# 1.net
KiCad netlist of a schematic drawn in EAGLE
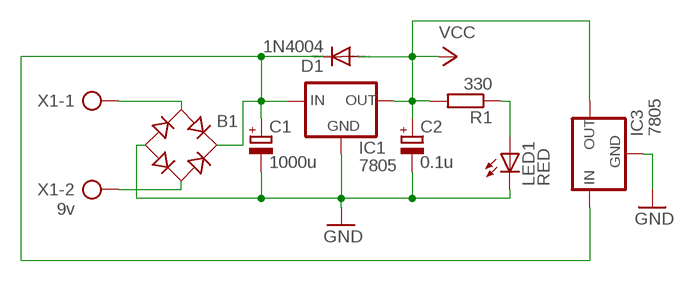
[diagram p0: schematic, sheet 1]
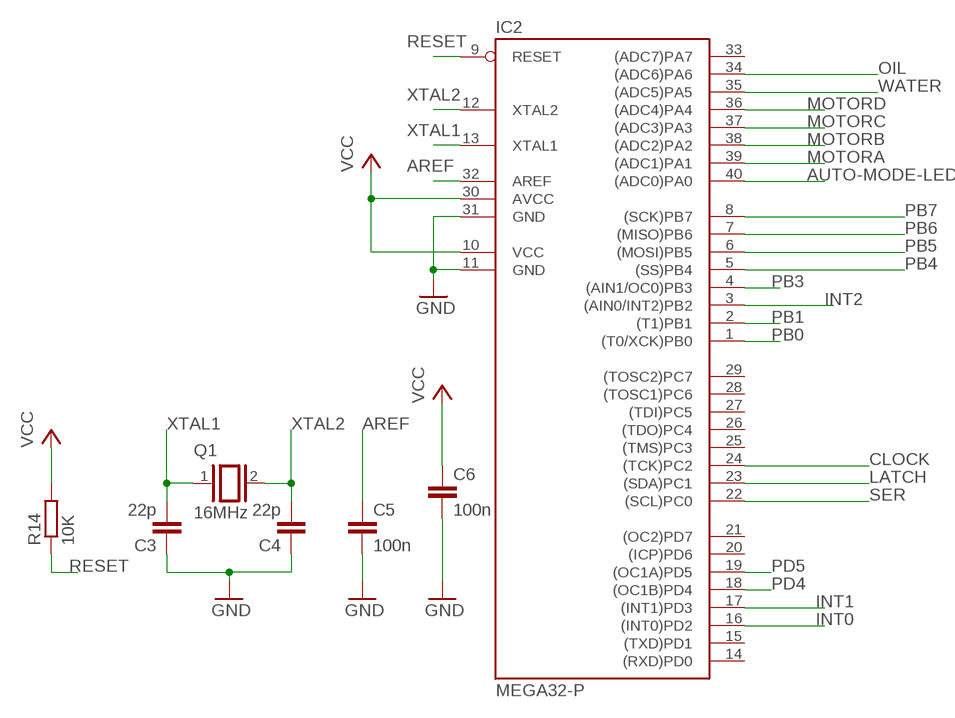
[diagram p1: schematic, sheet 2]
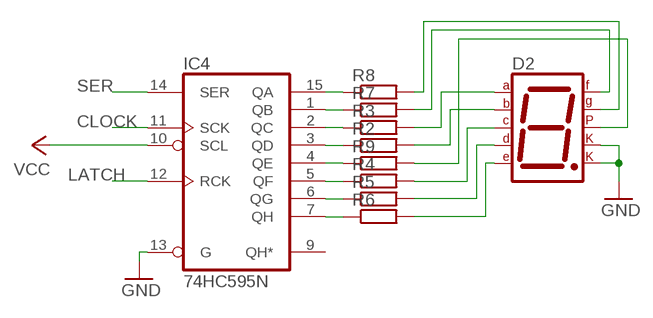
[diagram p2: schematic, sheet 3]
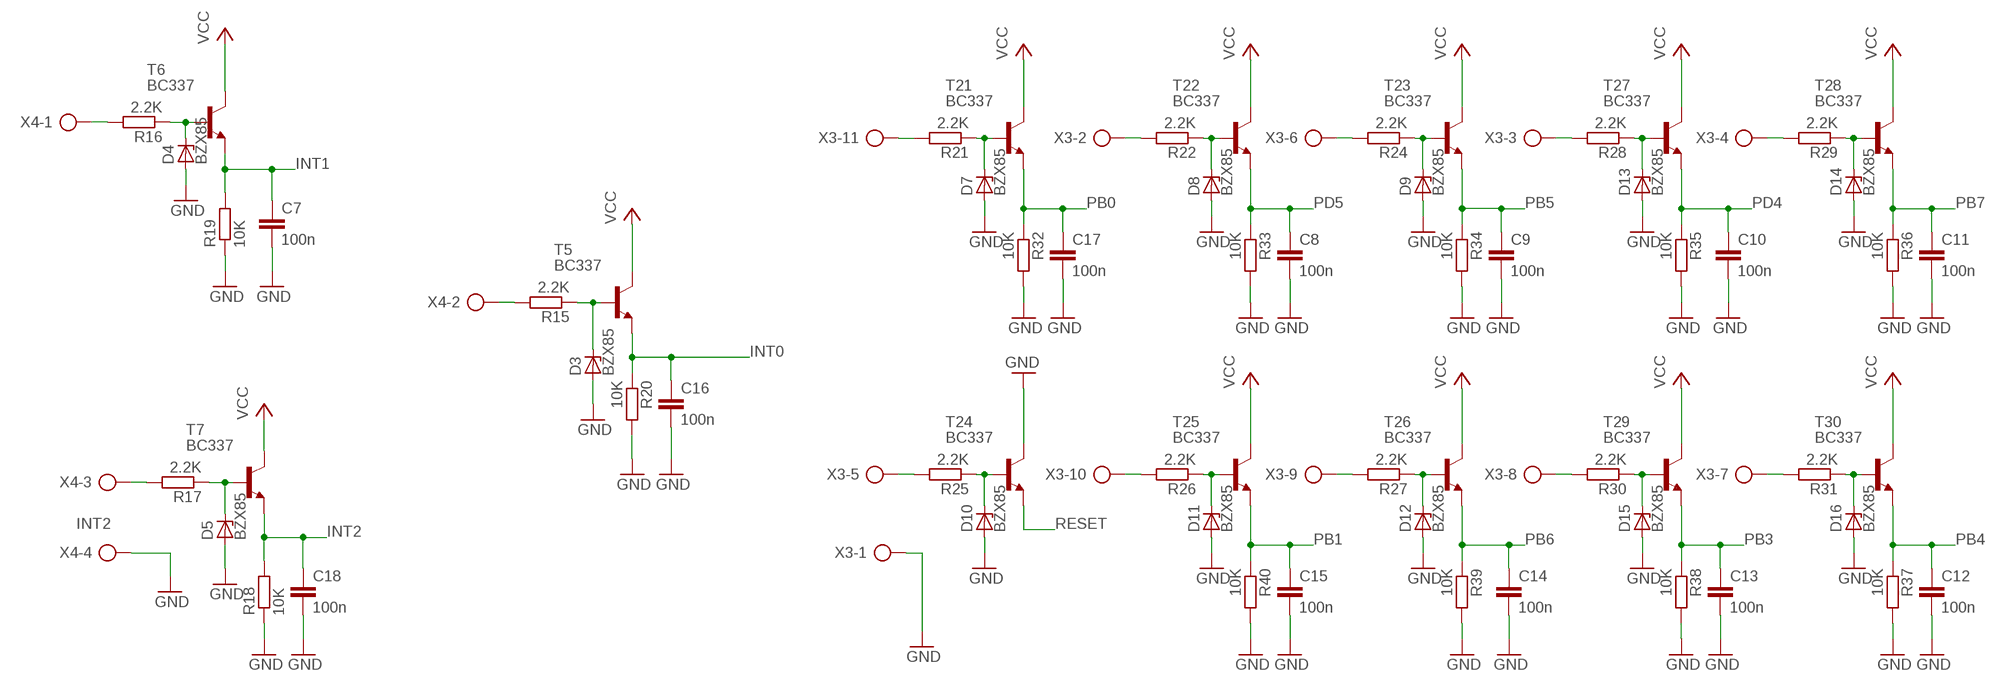
[diagram p3: schematic, sheet 4]
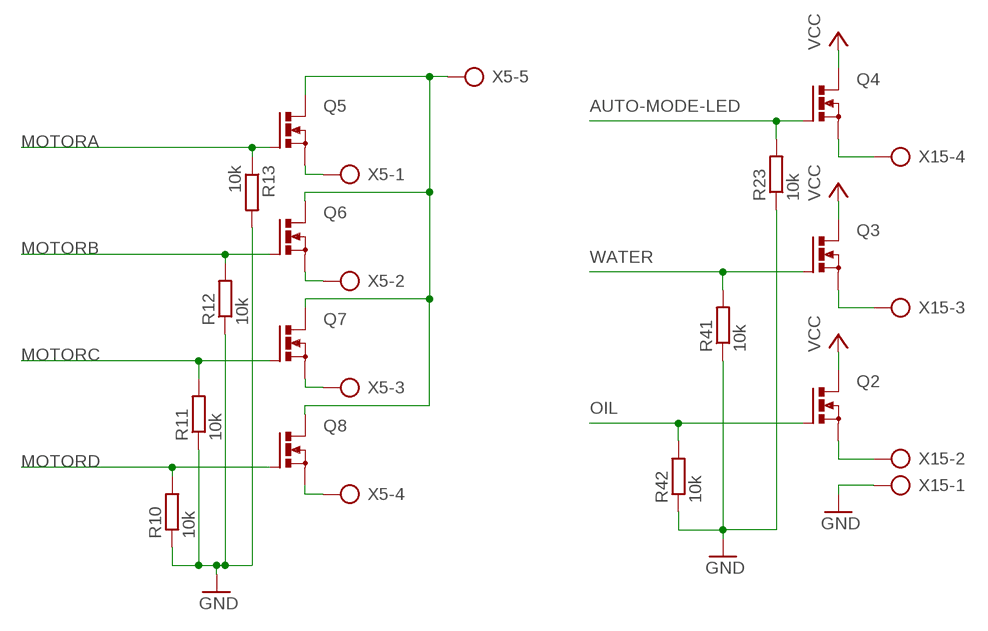
[diagram p4: schematic, sheet 5]

(export (version "E")
  (design (tool "Eeschema 10.0.6"))
  (components
    (comp (ref "Q2")
      (value "N-MOSFET-SO8S")
      (footprint "eagle-import:SO-08")
      (libsource (lib "eagle-import") (part "N-MOSFET-SO8S"))
    )
    (comp (ref "Q3")
      (value "N-MOSFET-SO8S")
      (footprint "eagle-import:SO-08")
      (libsource (lib "eagle-import") (part "N-MOSFET-SO8S"))
    )
    (comp (ref "Q4")
      (value "N-MOSFET-SO8S")
      (footprint "eagle-import:SO-08")
      (libsource (lib "eagle-import") (part "N-MOSFET-SO8S"))
    )
    (comp (ref "Q5")
      (value "N-MOSFET-SO8S")
      (footprint "eagle-import:SO-08")
      (libsource (lib "eagle-import") (part "N-MOSFET-SO8S"))
    )
    (comp (ref "Q6")
      (value "N-MOSFET-SO8S")
      (footprint "eagle-import:SO-08")
      (libsource (lib "eagle-import") (part "N-MOSFET-SO8S"))
    )
    (comp (ref "Q7")
      (value "N-MOSFET-SO8S")
      (footprint "eagle-import:SO-08")
      (libsource (lib "eagle-import") (part "N-MOSFET-SO8S"))
    )
    (comp (ref "Q8")
      (value "N-MOSFET-SO8S")
      (footprint "eagle-import:SO-08")
      (libsource (lib "eagle-import") (part "N-MOSFET-SO8S"))
    )
    (comp (ref "R10")
      (value "10k")
      (footprint "eagle-import:0204_7")
      (libsource (lib "eagle-import") (part "R-EU_0204/7"))
    )
    (comp (ref "R11")
      (value "10k")
      (footprint "eagle-import:0204_7")
      (libsource (lib "eagle-import") (part "R-EU_0204/7"))
    )
    (comp (ref "R12")
      (value "10k")
      (footprint "eagle-import:0204_7")
      (libsource (lib "eagle-import") (part "R-EU_0204/7"))
    )
    (comp (ref "R13")
      (value "10k")
      (footprint "eagle-import:0204_7")
      (libsource (lib "eagle-import") (part "R-EU_0204/7"))
    )
    (comp (ref "R23")
      (value "10k")
      (footprint "eagle-import:0204_7")
      (libsource (lib "eagle-import") (part "R-EU_0204/7"))
    )
    (comp (ref "R41")
      (value "10k")
      (footprint "eagle-import:0204_7")
      (libsource (lib "eagle-import") (part "R-EU_0204/7"))
    )
    (comp (ref "R42")
      (value "10k")
      (footprint "eagle-import:0204_7")
      (libsource (lib "eagle-import") (part "R-EU_0204/7"))
    )
    (comp (ref "X5")
      (value "AK500/5")
      (footprint "eagle-import:AK500_5")
      (libsource (lib "eagle-import") (part "AK500/5"))
    )
    (comp (ref "X15")
      (value "AK500/4")
      (footprint "eagle-import:AK500_4")
      (libsource (lib "eagle-import") (part "AK500/4"))
    )
    (comp (ref "C3")
      (value "22p")
      (footprint "eagle-import:C025-024X044")
      (libsource (lib "eagle-import") (part "C-EU025-024X044"))
    )
    (comp (ref "C4")
      (value "22p")
      (footprint "eagle-import:C025-024X044")
      (libsource (lib "eagle-import") (part "C-EU025-024X044"))
    )
    (comp (ref "C5")
      (value "100n")
      (footprint "eagle-import:C025-024X044")
      (libsource (lib "eagle-import") (part "C-EU025-024X044"))
    )
    (comp (ref "C6")
      (value "100n")
      (footprint "eagle-import:C025-024X044")
      (libsource (lib "eagle-import") (part "C-EU025-024X044"))
    )
    (comp (ref "IC2")
      (value "MEGA32-P")
      (footprint "eagle-import:DIL40")
      (fields (field (name "MPN") "ATMEGA32-16PU"))
      (libsource (lib "eagle-import") (part "MEGA32-P"))
    )
    (comp (ref "Q1")
      (value "16MHz")
      (footprint "eagle-import:Q")
      (libsource (lib "eagle-import") (part "XTAL"))
    )
    (comp (ref "R14")
      (value "10K")
      (footprint "eagle-import:0204_7")
      (libsource (lib "eagle-import") (part "R-EU_0204/7"))
    )
    (comp (ref "D2")
      (value "7SEG-CK")
      (footprint "eagle-import:7SEG-13")
      (libsource (lib "eagle-import") (part "7SEG-CK"))
    )
    (comp (ref "IC4")
      (value "74HC595N")
      (footprint "eagle-import:DIL16")
      (libsource (lib "eagle-import") (part "74595NHC"))
    )
    (comp (ref "R2")
      (value "R-EU_0204/7")
      (footprint "eagle-import:0204_7")
      (libsource (lib "eagle-import") (part "R-EU_0204/7"))
    )
    (comp (ref "R3")
      (value "R-EU_0204/7")
      (footprint "eagle-import:0204_7")
      (libsource (lib "eagle-import") (part "R-EU_0204/7"))
    )
    (comp (ref "R4")
      (value "R-EU_0204/7")
      (footprint "eagle-import:0204_7")
      (libsource (lib "eagle-import") (part "R-EU_0204/7"))
    )
    (comp (ref "R5")
      (value "R-EU_0204/7")
      (footprint "eagle-import:0204_7")
      (libsource (lib "eagle-import") (part "R-EU_0204/7"))
    )
    (comp (ref "R6")
      (value "R-EU_0204/7")
      (footprint "eagle-import:0204_7")
      (libsource (lib "eagle-import") (part "R-EU_0204/7"))
    )
    (comp (ref "R7")
      (value "R-EU_0204/7")
      (footprint "eagle-import:0204_7")
      (libsource (lib "eagle-import") (part "R-EU_0204/7"))
    )
    (comp (ref "R8")
      (value "R-EU_0204/7")
      (footprint "eagle-import:0204_7")
      (libsource (lib "eagle-import") (part "R-EU_0204/7"))
    )
    (comp (ref "R9")
      (value "R-EU_0204/7")
      (footprint "eagle-import:0204_7")
      (libsource (lib "eagle-import") (part "R-EU_0204/7"))
    )
    (comp (ref "B1")
      (value "RB1A")
      (footprint "eagle-import:RB1A")
      (libsource (lib "eagle-import") (part "RB1A"))
    )
    (comp (ref "C1")
      (value "1000u")
      (footprint "eagle-import:E3,5-8")
      (libsource (lib "eagle-import") (part "CPOL-EUE3.5-8"))
    )
    (comp (ref "C2")
      (value "0.1u")
      (footprint "eagle-import:E2-5")
      (libsource (lib "eagle-import") (part "CPOL-EUE2-5"))
    )
    (comp (ref "D1")
      (value "1N4004")
      (footprint "eagle-import:DO41-10")
      (libsource (lib "eagle-import") (part "1N4004"))
    )
    (comp (ref "IC1")
      (value "7805")
      (footprint "eagle-import:78XXS")
      (libsource (lib "eagle-import") (part "78XXS"))
    )
    (comp (ref "IC3")
      (value "7805")
      (footprint "eagle-import:78XXS")
      (libsource (lib "eagle-import") (part "78XXS"))
    )
    (comp (ref "LED1")
      (value "RED")
      (footprint "eagle-import:LED5MM")
      (libsource (lib "eagle-import") (part "LED5MM"))
    )
    (comp (ref "R1")
      (value "330")
      (footprint "eagle-import:0204_7")
      (libsource (lib "eagle-import") (part "R-EU_0204/7"))
    )
    (comp (ref "X1")
      (value "9v")
      (footprint "eagle-import:AK500_2")
      (libsource (lib "eagle-import") (part "AK500/2"))
    )
    (comp (ref "C7")
      (value "100n")
      (footprint "eagle-import:C025-024X044")
      (libsource (lib "eagle-import") (part "C-EU025-024X044"))
    )
    (comp (ref "C8")
      (value "100n")
      (footprint "eagle-import:C025-024X044")
      (libsource (lib "eagle-import") (part "C-EU025-024X044"))
    )
    (comp (ref "C9")
      (value "100n")
      (footprint "eagle-import:C025-024X044")
      (libsource (lib "eagle-import") (part "C-EU025-024X044"))
    )
    (comp (ref "C10")
      (value "100n")
      (footprint "eagle-import:C025-024X044")
      (libsource (lib "eagle-import") (part "C-EU025-024X044"))
    )
    (comp (ref "C11")
      (value "100n")
      (footprint "eagle-import:C025-024X044")
      (libsource (lib "eagle-import") (part "C-EU025-024X044"))
    )
    (comp (ref "C12")
      (value "100n")
      (footprint "eagle-import:C025-024X044")
      (libsource (lib "eagle-import") (part "C-EU025-024X044"))
    )
    (comp (ref "C13")
      (value "100n")
      (footprint "eagle-import:C025-024X044")
      (libsource (lib "eagle-import") (part "C-EU025-024X044"))
    )
    (comp (ref "C14")
      (value "100n")
      (footprint "eagle-import:C025-024X044")
      (libsource (lib "eagle-import") (part "C-EU025-024X044"))
    )
    (comp (ref "C15")
      (value "100n")
      (footprint "eagle-import:C025-024X044")
      (libsource (lib "eagle-import") (part "C-EU025-024X044"))
    )
    (comp (ref "C16")
      (value "100n")
      (footprint "eagle-import:C025-024X044")
      (libsource (lib "eagle-import") (part "C-EU025-024X044"))
    )
    (comp (ref "C17")
      (value "100n")
      (footprint "eagle-import:C025-024X044")
      (libsource (lib "eagle-import") (part "C-EU025-024X044"))
    )
    (comp (ref "C18")
      (value "100n")
      (footprint "eagle-import:C025-024X044")
      (libsource (lib "eagle-import") (part "C-EU025-024X044"))
    )
    (comp (ref "D3")
      (value "BZX85")
      (footprint "eagle-import:DO41Z10")
      (libsource (lib "eagle-import") (part "BZX85"))
    )
    (comp (ref "D4")
      (value "BZX85")
      (footprint "eagle-import:DO41Z10")
      (libsource (lib "eagle-import") (part "BZX85"))
    )
    (comp (ref "D5")
      (value "BZX85")
      (footprint "eagle-import:DO41Z10")
      (libsource (lib "eagle-import") (part "BZX85"))
    )
    (comp (ref "D7")
      (value "BZX85")
      (footprint "eagle-import:DO41Z10")
      (libsource (lib "eagle-import") (part "BZX85"))
    )
    (comp (ref "D8")
      (value "BZX85")
      (footprint "eagle-import:DO41Z10")
      (libsource (lib "eagle-import") (part "BZX85"))
    )
    (comp (ref "D9")
      (value "BZX85")
      (footprint "eagle-import:DO41Z10")
      (libsource (lib "eagle-import") (part "BZX85"))
    )
    (comp (ref "D10")
      (value "BZX85")
      (footprint "eagle-import:DO41Z10")
      (libsource (lib "eagle-import") (part "BZX85"))
    )
    (comp (ref "D11")
      (value "BZX85")
      (footprint "eagle-import:DO41Z10")
      (libsource (lib "eagle-import") (part "BZX85"))
    )
    (comp (ref "D12")
      (value "BZX85")
      (footprint "eagle-import:DO41Z10")
      (libsource (lib "eagle-import") (part "BZX85"))
    )
    (comp (ref "D13")
      (value "BZX85")
      (footprint "eagle-import:DO41Z10")
      (libsource (lib "eagle-import") (part "BZX85"))
    )
    (comp (ref "D14")
      (value "BZX85")
      (footprint "eagle-import:DO41Z10")
      (libsource (lib "eagle-import") (part "BZX85"))
    )
    (comp (ref "D15")
      (value "BZX85")
      (footprint "eagle-import:DO41Z10")
      (libsource (lib "eagle-import") (part "BZX85"))
    )
    (comp (ref "D16")
      (value "BZX85")
      (footprint "eagle-import:DO41Z10")
      (libsource (lib "eagle-import") (part "BZX85"))
    )
    (comp (ref "R15")
      (value "2.2K")
      (footprint "eagle-import:0207_10")
      (libsource (lib "eagle-import") (part "R-EU_0207/10"))
    )
    (comp (ref "R16")
      (value "2.2K")
      (footprint "eagle-import:0207_10")
      (libsource (lib "eagle-import") (part "R-EU_0207/10"))
    )
    (comp (ref "R17")
      (value "2.2K")
      (footprint "eagle-import:0207_10")
      (libsource (lib "eagle-import") (part "R-EU_0207/10"))
    )
    (comp (ref "R18")
      (value "10K")
      (footprint "eagle-import:0204_7")
      (libsource (lib "eagle-import") (part "R-EU_0204/7"))
    )
    (comp (ref "R19")
      (value "10K")
      (footprint "eagle-import:0204_7")
      (libsource (lib "eagle-import") (part "R-EU_0204/7"))
    )
    (comp (ref "R20")
      (value "10K")
      (footprint "eagle-import:0204_7")
      (libsource (lib "eagle-import") (part "R-EU_0204/7"))
    )
    (comp (ref "R21")
      (value "2.2K")
      (footprint "eagle-import:0207_10")
      (libsource (lib "eagle-import") (part "R-EU_0207/10"))
    )
    (comp (ref "R22")
      (value "2.2K")
      (footprint "eagle-import:0207_10")
      (libsource (lib "eagle-import") (part "R-EU_0207/10"))
    )
    (comp (ref "R24")
      (value "2.2K")
      (footprint "eagle-import:0207_10")
      (libsource (lib "eagle-import") (part "R-EU_0207/10"))
    )
    (comp (ref "R25")
      (value "2.2K")
      (footprint "eagle-import:0207_10")
      (libsource (lib "eagle-import") (part "R-EU_0207/10"))
    )
    (comp (ref "R26")
      (value "2.2K")
      (footprint "eagle-import:0207_10")
      (libsource (lib "eagle-import") (part "R-EU_0207/10"))
    )
    (comp (ref "R27")
      (value "2.2K")
      (footprint "eagle-import:0207_10")
      (libsource (lib "eagle-import") (part "R-EU_0207/10"))
    )
    (comp (ref "R28")
      (value "2.2K")
      (footprint "eagle-import:0207_10")
      (libsource (lib "eagle-import") (part "R-EU_0207/10"))
    )
    (comp (ref "R29")
      (value "2.2K")
      (footprint "eagle-import:0207_10")
      (libsource (lib "eagle-import") (part "R-EU_0207/10"))
    )
    (comp (ref "R30")
      (value "2.2K")
      (footprint "eagle-import:0207_10")
      (libsource (lib "eagle-import") (part "R-EU_0207/10"))
    )
    (comp (ref "R31")
      (value "2.2K")
      (footprint "eagle-import:0207_10")
      (libsource (lib "eagle-import") (part "R-EU_0207/10"))
    )
    (comp (ref "R32")
      (value "10K")
      (footprint "eagle-import:0204_7")
      (libsource (lib "eagle-import") (part "R-EU_0204/7"))
    )
    (comp (ref "R33")
      (value "10K")
      (footprint "eagle-import:0204_7")
      (libsource (lib "eagle-import") (part "R-EU_0204/7"))
    )
    (comp (ref "R34")
      (value "10K")
      (footprint "eagle-import:0204_7")
      (libsource (lib "eagle-import") (part "R-EU_0204/7"))
    )
    (comp (ref "R35")
      (value "10K")
      (footprint "eagle-import:0204_7")
      (libsource (lib "eagle-import") (part "R-EU_0204/7"))
    )
    (comp (ref "R36")
      (value "10K")
      (footprint "eagle-import:0204_7")
      (libsource (lib "eagle-import") (part "R-EU_0204/7"))
    )
    (comp (ref "R37")
      (value "10K")
      (footprint "eagle-import:0204_7")
      (libsource (lib "eagle-import") (part "R-EU_0204/7"))
    )
    (comp (ref "R38")
      (value "10K")
      (footprint "eagle-import:0204_7")
      (libsource (lib "eagle-import") (part "R-EU_0204/7"))
    )
    (comp (ref "R39")
      (value "10K")
      (footprint "eagle-import:0204_7")
      (libsource (lib "eagle-import") (part "R-EU_0204/7"))
    )
    (comp (ref "R40")
      (value "10K")
      (footprint "eagle-import:0204_7")
      (libsource (lib "eagle-import") (part "R-EU_0204/7"))
    )
    (comp (ref "T5")
      (value "BC337")
      (footprint "eagle-import:TO92")
      (libsource (lib "eagle-import") (part "BC337"))
    )
    (comp (ref "T6")
      (value "BC337")
      (footprint "eagle-import:TO92")
      (libsource (lib "eagle-import") (part "BC337"))
    )
    (comp (ref "T7")
      (value "BC337")
      (footprint "eagle-import:TO92")
      (libsource (lib "eagle-import") (part "BC337"))
    )
    (comp (ref "T21")
      (value "BC337")
      (footprint "eagle-import:TO92")
      (libsource (lib "eagle-import") (part "BC337"))
    )
    (comp (ref "T22")
      (value "BC337")
      (footprint "eagle-import:TO92")
      (libsource (lib "eagle-import") (part "BC337"))
    )
    (comp (ref "T23")
      (value "BC337")
      (footprint "eagle-import:TO92")
      (libsource (lib "eagle-import") (part "BC337"))
    )
    (comp (ref "T24")
      (value "BC337")
      (footprint "eagle-import:TO92")
      (libsource (lib "eagle-import") (part "BC337"))
    )
    (comp (ref "T25")
      (value "BC337")
      (footprint "eagle-import:TO92")
      (libsource (lib "eagle-import") (part "BC337"))
    )
    (comp (ref "T26")
      (value "BC337")
      (footprint "eagle-import:TO92")
      (libsource (lib "eagle-import") (part "BC337"))
    )
    (comp (ref "T27")
      (value "BC337")
      (footprint "eagle-import:TO92")
      (libsource (lib "eagle-import") (part "BC337"))
    )
    (comp (ref "T28")
      (value "BC337")
      (footprint "eagle-import:TO92")
      (libsource (lib "eagle-import") (part "BC337"))
    )
    (comp (ref "T29")
      (value "BC337")
      (footprint "eagle-import:TO92")
      (libsource (lib "eagle-import") (part "BC337"))
    )
    (comp (ref "T30")
      (value "BC337")
      (footprint "eagle-import:TO92")
      (libsource (lib "eagle-import") (part "BC337"))
    )
    (comp (ref "X3")
      (value "AK500/11")
      (footprint "eagle-import:AK500_11")
      (libsource (lib "eagle-import") (part "AK500/11"))
    )
    (comp (ref "X4")
      (value "AK500/4")
      (footprint "eagle-import:AK500_4")
      (libsource (lib "eagle-import") (part "AK500/4"))
    )
  )
  (nets
    (net (code "1") (name "AREF") (class "Default")
      (node (ref "C5") (pin "1") (pinfunction "1_1") (pintype "passive"))
      (node (ref "IC2") (pin "32") (pinfunction "AREF_32") (pintype "passive"))
    )
    (net (code "2") (name "AUTO-MODE-LED") (class "Default")
      (node (ref "IC2") (pin "40") (pinfunction "(ADC0)PA0_40") (pintype "bidirectional"))
      (node (ref "Q4") (pin "4") (pinfunction "G_4") (pintype "passive"))
      (node (ref "R23") (pin "2") (pinfunction "2_2") (pintype "passive"))
    )
    (net (code "3") (name "CLOCK") (class "Default")
      (node (ref "IC2") (pin "24") (pinfunction "(TCK)PC2_24") (pintype "bidirectional"))
      (node (ref "IC4") (pin "11") (pinfunction "SCK_11") (pintype "input"))
    )
    (net (code "4") (name "GND") (class "Default")
      (node (ref "B1") (pin "-") (pinfunction "-_-") (pintype "passive"))
      (node (ref "C1") (pin "-") (pinfunction "-_-") (pintype "passive"))
      (node (ref "C10") (pin "2") (pinfunction "2_2") (pintype "passive"))
      (node (ref "C11") (pin "2") (pinfunction "2_2") (pintype "passive"))
      (node (ref "C12") (pin "2") (pinfunction "2_2") (pintype "passive"))
      (node (ref "C13") (pin "2") (pinfunction "2_2") (pintype "passive"))
      (node (ref "C14") (pin "2") (pinfunction "2_2") (pintype "passive"))
      (node (ref "C15") (pin "2") (pinfunction "2_2") (pintype "passive"))
      (node (ref "C16") (pin "2") (pinfunction "2_2") (pintype "passive"))
      (node (ref "C17") (pin "2") (pinfunction "2_2") (pintype "passive"))
      (node (ref "C18") (pin "2") (pinfunction "2_2") (pintype "passive"))
      (node (ref "C2") (pin "-") (pinfunction "-_-") (pintype "passive"))
      (node (ref "C3") (pin "1") (pinfunction "1_1") (pintype "passive"))
      (node (ref "C4") (pin "1") (pinfunction "1_1") (pintype "passive"))
      (node (ref "C5") (pin "2") (pinfunction "2_2") (pintype "passive"))
      (node (ref "C6") (pin "2") (pinfunction "2_2") (pintype "passive"))
      (node (ref "C7") (pin "2") (pinfunction "2_2") (pintype "passive"))
      (node (ref "C8") (pin "2") (pinfunction "2_2") (pintype "passive"))
      (node (ref "C9") (pin "2") (pinfunction "2_2") (pintype "passive"))
      (node (ref "D10") (pin "A") (pinfunction "A_A") (pintype "passive"))
      (node (ref "D11") (pin "A") (pinfunction "A_A") (pintype "passive"))
      (node (ref "D12") (pin "A") (pinfunction "A_A") (pintype "passive"))
      (node (ref "D13") (pin "A") (pinfunction "A_A") (pintype "passive"))
      (node (ref "D14") (pin "A") (pinfunction "A_A") (pintype "passive"))
      (node (ref "D15") (pin "A") (pinfunction "A_A") (pintype "passive"))
      (node (ref "D16") (pin "A") (pinfunction "A_A") (pintype "passive"))
      (node (ref "D2") (pin "3") (pinfunction "CK1_3") (pintype "passive"))
      (node (ref "D2") (pin "8") (pinfunction "CK2_8") (pintype "passive"))
      (node (ref "D3") (pin "A") (pinfunction "A_A") (pintype "passive"))
      (node (ref "D4") (pin "A") (pinfunction "A_A") (pintype "passive"))
      (node (ref "D5") (pin "A") (pinfunction "A_A") (pintype "passive"))
      (node (ref "D7") (pin "A") (pinfunction "A_A") (pintype "passive"))
      (node (ref "D8") (pin "A") (pinfunction "A_A") (pintype "passive"))
      (node (ref "D9") (pin "A") (pinfunction "A_A") (pintype "passive"))
      (node (ref "IC1") (pin "GND") (pinfunction "GND_GND") (pintype "input"))
      (node (ref "IC2") (pin "11") (pinfunction "GND_11") (pintype "power_in"))
      (node (ref "IC2") (pin "31") (pinfunction "GND_31") (pintype "power_in"))
      (node (ref "IC3") (pin "GND") (pinfunction "GND_GND") (pintype "input"))
      (node (ref "IC4") (pin "13") (pinfunction "G_13") (pintype "input"))
      (node (ref "LED1") (pin "K") (pinfunction "C_K") (pintype "passive"))
      (node (ref "R10") (pin "1") (pinfunction "1_1") (pintype "passive"))
      (node (ref "R11") (pin "1") (pinfunction "1_1") (pintype "passive"))
      (node (ref "R12") (pin "1") (pinfunction "1_1") (pintype "passive"))
      (node (ref "R13") (pin "2") (pinfunction "2_2") (pintype "passive"))
      (node (ref "R18") (pin "1") (pinfunction "1_1") (pintype "passive"))
      (node (ref "R19") (pin "1") (pinfunction "1_1") (pintype "passive"))
      (node (ref "R20") (pin "2") (pinfunction "2_2") (pintype "passive"))
      (node (ref "R23") (pin "1") (pinfunction "1_1") (pintype "passive"))
      (node (ref "R32") (pin "2") (pinfunction "2_2") (pintype "passive"))
      (node (ref "R33") (pin "2") (pinfunction "2_2") (pintype "passive"))
      (node (ref "R34") (pin "2") (pinfunction "2_2") (pintype "passive"))
      (node (ref "R35") (pin "2") (pinfunction "2_2") (pintype "passive"))
      (node (ref "R36") (pin "2") (pinfunction "2_2") (pintype "passive"))
      (node (ref "R37") (pin "2") (pinfunction "2_2") (pintype "passive"))
      (node (ref "R38") (pin "2") (pinfunction "2_2") (pintype "passive"))
      (node (ref "R39") (pin "2") (pinfunction "2_2") (pintype "passive"))
      (node (ref "R40") (pin "2") (pinfunction "2_2") (pintype "passive"))
      (node (ref "R41") (pin "1") (pinfunction "1_1") (pintype "passive"))
      (node (ref "R42") (pin "1") (pinfunction "1_1") (pintype "passive"))
      (node (ref "T24") (pin "3") (pinfunction "C_3") (pintype "passive"))
      (node (ref "X15") (pin "1") (pinfunction "KL_1") (pintype "passive"))
      (node (ref "X3") (pin "1") (pinfunction "KL_1") (pintype "passive"))
      (node (ref "X4") (pin "4") (pinfunction "KL_4") (pintype "passive"))
    )
    (net (code "5") (name "INT0") (class "Default")
      (node (ref "C16") (pin "1") (pinfunction "1_1") (pintype "passive"))
      (node (ref "IC2") (pin "16") (pinfunction "(INT0)PD2_16") (pintype "bidirectional"))
      (node (ref "R20") (pin "1") (pinfunction "1_1") (pintype "passive"))
      (node (ref "T5") (pin "1") (pinfunction "E_1") (pintype "passive"))
    )
    (net (code "6") (name "INT1") (class "Default")
      (node (ref "C7") (pin "1") (pinfunction "1_1") (pintype "passive"))
      (node (ref "IC2") (pin "17") (pinfunction "(INT1)PD3_17") (pintype "bidirectional"))
      (node (ref "R19") (pin "2") (pinfunction "2_2") (pintype "passive"))
      (node (ref "T6") (pin "1") (pinfunction "E_1") (pintype "passive"))
    )
    (net (code "7") (name "INT2") (class "Default")
      (node (ref "C18") (pin "1") (pinfunction "1_1") (pintype "passive"))
      (node (ref "IC2") (pin "3") (pinfunction "(AIN0/INT2)PB2_3") (pintype "bidirectional"))
      (node (ref "R18") (pin "2") (pinfunction "2_2") (pintype "passive"))
      (node (ref "T7") (pin "1") (pinfunction "E_1") (pintype "passive"))
    )
    (net (code "8") (name "LATCH") (class "Default")
      (node (ref "IC2") (pin "23") (pinfunction "(SDA)PC1_23") (pintype "bidirectional"))
      (node (ref "IC4") (pin "12") (pinfunction "RCK_12") (pintype "input"))
    )
    (net (code "9") (name "MOTORA") (class "Default")
      (node (ref "IC2") (pin "39") (pinfunction "(ADC1)PA1_39") (pintype "bidirectional"))
      (node (ref "Q5") (pin "4") (pinfunction "G_4") (pintype "passive"))
      (node (ref "R13") (pin "1") (pinfunction "1_1") (pintype "passive"))
    )
    (net (code "10") (name "MOTORB") (class "Default")
      (node (ref "IC2") (pin "38") (pinfunction "(ADC2)PA2_38") (pintype "bidirectional"))
      (node (ref "Q6") (pin "4") (pinfunction "G_4") (pintype "passive"))
      (node (ref "R12") (pin "2") (pinfunction "2_2") (pintype "passive"))
    )
    (net (code "11") (name "MOTORC") (class "Default")
      (node (ref "IC2") (pin "37") (pinfunction "(ADC3)PA3_37") (pintype "bidirectional"))
      (node (ref "Q7") (pin "4") (pinfunction "G_4") (pintype "passive"))
      (node (ref "R11") (pin "2") (pinfunction "2_2") (pintype "passive"))
    )
    (net (code "12") (name "MOTORD") (class "Default")
      (node (ref "IC2") (pin "36") (pinfunction "(ADC4)PA4_36") (pintype "bidirectional"))
      (node (ref "Q8") (pin "4") (pinfunction "G_4") (pintype "passive"))
      (node (ref "R10") (pin "2") (pinfunction "2_2") (pintype "passive"))
    )
    (net (code "13") (name "Net-(B1-Pad+)") (class "Default")
      (node (ref "B1") (pin "+") (pinfunction "+_+") (pintype "passive"))
      (node (ref "C1") (pin "+") (pinfunction "+_+") (pintype "passive"))
      (node (ref "D1") (pin "C") (pinfunction "C_C") (pintype "passive"))
      (node (ref "IC1") (pin "IN") (pinfunction "IN_IN") (pintype "input"))
      (node (ref "IC3") (pin "IN") (pinfunction "IN_IN") (pintype "input"))
    )
    (net (code "14") (name "Net-(D2-A)") (class "Default")
      (node (ref "D2") (pin "7") (pinfunction "A_7") (pintype "passive"))
      (node (ref "R3") (pin "2") (pinfunction "2_2") (pintype "passive"))
    )
    (net (code "15") (name "Net-(D2-B)") (class "Default")
      (node (ref "D2") (pin "6") (pinfunction "B_6") (pintype "passive"))
      (node (ref "R2") (pin "2") (pinfunction "2_2") (pintype "passive"))
    )
    (net (code "16") (name "Net-(D2-C)") (class "Default")
      (node (ref "D2") (pin "4") (pinfunction "C_4") (pintype "passive"))
      (node (ref "R4") (pin "2") (pinfunction "2_2") (pintype "passive"))
    )
    (net (code "17") (name "Net-(D2-D)") (class "Default")
      (node (ref "D2") (pin "2") (pinfunction "D_2") (pintype "passive"))
      (node (ref "R5") (pin "2") (pinfunction "2_2") (pintype "passive"))
    )
    (net (code "18") (name "Net-(D2-DP)") (class "Default")
      (node (ref "D2") (pin "5") (pinfunction "DP_5") (pintype "passive"))
      (node (ref "R9") (pin "2") (pinfunction "2_2") (pintype "passive"))
    )
    (net (code "19") (name "Net-(D2-E)") (class "Default")
      (node (ref "D2") (pin "1") (pinfunction "E_1") (pintype "passive"))
      (node (ref "R6") (pin "2") (pinfunction "2_2") (pintype "passive"))
    )
    (net (code "20") (name "Net-(D2-F)") (class "Default")
      (node (ref "D2") (pin "9") (pinfunction "F_9") (pintype "passive"))
      (node (ref "R7") (pin "2") (pinfunction "2_2") (pintype "passive"))
    )
    (net (code "21") (name "Net-(D2-G)") (class "Default")
      (node (ref "D2") (pin "10") (pinfunction "G_10") (pintype "passive"))
      (node (ref "R8") (pin "2") (pinfunction "2_2") (pintype "passive"))
    )
    (net (code "22") (name "Net-(IC4A-QA)") (class "Default")
      (node (ref "IC4") (pin "15") (pinfunction "QA_15") (pintype "tri_state"))
      (node (ref "R8") (pin "1") (pinfunction "1_1") (pintype "passive"))
    )
    (net (code "23") (name "Net-(IC4A-QB)") (class "Default")
      (node (ref "IC4") (pin "1") (pinfunction "QB_1") (pintype "tri_state"))
      (node (ref "R7") (pin "1") (pinfunction "1_1") (pintype "passive"))
    )
    (net (code "24") (name "Net-(IC4A-QC)") (class "Default")
      (node (ref "IC4") (pin "2") (pinfunction "QC_2") (pintype "tri_state"))
      (node (ref "R3") (pin "1") (pinfunction "1_1") (pintype "passive"))
    )
    (net (code "25") (name "Net-(IC4A-QD)") (class "Default")
      (node (ref "IC4") (pin "3") (pinfunction "QD_3") (pintype "tri_state"))
      (node (ref "R2") (pin "1") (pinfunction "1_1") (pintype "passive"))
    )
    (net (code "26") (name "Net-(IC4A-QE)") (class "Default")
      (node (ref "IC4") (pin "4") (pinfunction "QE_4") (pintype "tri_state"))
      (node (ref "R9") (pin "1") (pinfunction "1_1") (pintype "passive"))
    )
    (net (code "27") (name "Net-(IC4A-QF)") (class "Default")
      (node (ref "IC4") (pin "5") (pinfunction "QF_5") (pintype "tri_state"))
      (node (ref "R4") (pin "1") (pinfunction "1_1") (pintype "passive"))
    )
    (net (code "28") (name "Net-(IC4A-QG)") (class "Default")
      (node (ref "IC4") (pin "6") (pinfunction "QG_6") (pintype "tri_state"))
      (node (ref "R5") (pin "1") (pinfunction "1_1") (pintype "passive"))
    )
    (net (code "29") (name "Net-(IC4A-QH)") (class "Default")
      (node (ref "IC4") (pin "7") (pinfunction "QH_7") (pintype "tri_state"))
      (node (ref "R6") (pin "1") (pinfunction "1_1") (pintype "passive"))
    )
    (net (code "30") (name "Net-(LED1-PadA)") (class "Default")
      (node (ref "LED1") (pin "A") (pinfunction "A_A") (pintype "passive"))
      (node (ref "R1") (pin "1") (pinfunction "1_1") (pintype "passive"))
    )
    (net (code "31") (name "Net-(T5-B)") (class "Default")
      (node (ref "D3") (pin "C") (pinfunction "C_C") (pintype "passive"))
      (node (ref "R15") (pin "1") (pinfunction "1_1") (pintype "passive"))
      (node (ref "T5") (pin "2") (pinfunction "B_2") (pintype "passive"))
    )
    (net (code "32") (name "Net-(T6-B)") (class "Default")
      (node (ref "D4") (pin "C") (pinfunction "C_C") (pintype "passive"))
      (node (ref "R16") (pin "1") (pinfunction "1_1") (pintype "passive"))
      (node (ref "T6") (pin "2") (pinfunction "B_2") (pintype "passive"))
    )
    (net (code "33") (name "Net-(T7-B)") (class "Default")
      (node (ref "D5") (pin "C") (pinfunction "C_C") (pintype "passive"))
      (node (ref "R17") (pin "1") (pinfunction "1_1") (pintype "passive"))
      (node (ref "T7") (pin "2") (pinfunction "B_2") (pintype "passive"))
    )
    (net (code "34") (name "Net-(T21-B)") (class "Default")
      (node (ref "D7") (pin "C") (pinfunction "C_C") (pintype "passive"))
      (node (ref "R21") (pin "1") (pinfunction "1_1") (pintype "passive"))
      (node (ref "T21") (pin "2") (pinfunction "B_2") (pintype "passive"))
    )
    (net (code "35") (name "Net-(T22-B)") (class "Default")
      (node (ref "D8") (pin "C") (pinfunction "C_C") (pintype "passive"))
      (node (ref "R22") (pin "1") (pinfunction "1_1") (pintype "passive"))
      (node (ref "T22") (pin "2") (pinfunction "B_2") (pintype "passive"))
    )
    (net (code "36") (name "Net-(T23-B)") (class "Default")
      (node (ref "D9") (pin "C") (pinfunction "C_C") (pintype "passive"))
      (node (ref "R24") (pin "1") (pinfunction "1_1") (pintype "passive"))
      (node (ref "T23") (pin "2") (pinfunction "B_2") (pintype "passive"))
    )
    (net (code "37") (name "Net-(T24-B)") (class "Default")
      (node (ref "D10") (pin "C") (pinfunction "C_C") (pintype "passive"))
      (node (ref "R25") (pin "1") (pinfunction "1_1") (pintype "passive"))
      (node (ref "T24") (pin "2") (pinfunction "B_2") (pintype "passive"))
    )
    (net (code "38") (name "Net-(T25-B)") (class "Default")
      (node (ref "D11") (pin "C") (pinfunction "C_C") (pintype "passive"))
      (node (ref "R26") (pin "1") (pinfunction "1_1") (pintype "passive"))
      (node (ref "T25") (pin "2") (pinfunction "B_2") (pintype "passive"))
    )
    (net (code "39") (name "Net-(T26-B)") (class "Default")
      (node (ref "D12") (pin "C") (pinfunction "C_C") (pintype "passive"))
      (node (ref "R27") (pin "1") (pinfunction "1_1") (pintype "passive"))
      (node (ref "T26") (pin "2") (pinfunction "B_2") (pintype "passive"))
    )
    (net (code "40") (name "Net-(T27-B)") (class "Default")
      (node (ref "D13") (pin "C") (pinfunction "C_C") (pintype "passive"))
      (node (ref "R28") (pin "1") (pinfunction "1_1") (pintype "passive"))
      (node (ref "T27") (pin "2") (pinfunction "B_2") (pintype "passive"))
    )
    (net (code "41") (name "Net-(T28-B)") (class "Default")
      (node (ref "D14") (pin "C") (pinfunction "C_C") (pintype "passive"))
      (node (ref "R29") (pin "1") (pinfunction "1_1") (pintype "passive"))
      (node (ref "T28") (pin "2") (pinfunction "B_2") (pintype "passive"))
    )
    (net (code "42") (name "Net-(T29-B)") (class "Default")
      (node (ref "D15") (pin "C") (pinfunction "C_C") (pintype "passive"))
      (node (ref "R30") (pin "1") (pinfunction "1_1") (pintype "passive"))
      (node (ref "T29") (pin "2") (pinfunction "B_2") (pintype "passive"))
    )
    (net (code "43") (name "Net-(T30-B)") (class "Default")
      (node (ref "D16") (pin "C") (pinfunction "C_C") (pintype "passive"))
      (node (ref "R31") (pin "1") (pinfunction "1_1") (pintype "passive"))
      (node (ref "T30") (pin "2") (pinfunction "B_2") (pintype "passive"))
    )
    (net (code "44") (name "Net-(X1A-KL)") (class "Default")
      (node (ref "B1") (pin "AC1") (pinfunction "AC1_AC1") (pintype "passive"))
      (node (ref "X1") (pin "1") (pinfunction "KL_1") (pintype "passive"))
    )
    (net (code "45") (name "Net-(X1B-KL)") (class "Default")
      (node (ref "B1") (pin "AC2") (pinfunction "AC2_AC2") (pintype "passive"))
      (node (ref "X1") (pin "2") (pinfunction "KL_2") (pintype "passive"))
    )
    (net (code "46") (name "Net-(X3B-KL)") (class "Default")
      (node (ref "R26") (pin "2") (pinfunction "2_2") (pintype "passive"))
      (node (ref "X3") (pin "10") (pinfunction "KL_10") (pintype "passive"))
    )
    (net (code "47") (name "Net-(X3C-KL)") (class "Default")
      (node (ref "R21") (pin "2") (pinfunction "2_2") (pintype "passive"))
      (node (ref "X3") (pin "11") (pinfunction "KL_11") (pintype "passive"))
    )
    (net (code "48") (name "Net-(X3D-KL)") (class "Default")
      (node (ref "R22") (pin "2") (pinfunction "2_2") (pintype "passive"))
      (node (ref "X3") (pin "2") (pinfunction "KL_2") (pintype "passive"))
    )
    (net (code "49") (name "Net-(X3E-KL)") (class "Default")
      (node (ref "R28") (pin "2") (pinfunction "2_2") (pintype "passive"))
      (node (ref "X3") (pin "3") (pinfunction "KL_3") (pintype "passive"))
    )
    (net (code "50") (name "Net-(X3F-KL)") (class "Default")
      (node (ref "R29") (pin "2") (pinfunction "2_2") (pintype "passive"))
      (node (ref "X3") (pin "4") (pinfunction "KL_4") (pintype "passive"))
    )
    (net (code "51") (name "Net-(X3G-KL)") (class "Default")
      (node (ref "R25") (pin "2") (pinfunction "2_2") (pintype "passive"))
      (node (ref "X3") (pin "5") (pinfunction "KL_5") (pintype "passive"))
    )
    (net (code "52") (name "Net-(X3H-KL)") (class "Default")
      (node (ref "R24") (pin "2") (pinfunction "2_2") (pintype "passive"))
      (node (ref "X3") (pin "6") (pinfunction "KL_6") (pintype "passive"))
    )
    (net (code "53") (name "Net-(X3I-KL)") (class "Default")
      (node (ref "R31") (pin "2") (pinfunction "2_2") (pintype "passive"))
      (node (ref "X3") (pin "7") (pinfunction "KL_7") (pintype "passive"))
    )
    (net (code "54") (name "Net-(X3J-KL)") (class "Default")
      (node (ref "R30") (pin "2") (pinfunction "2_2") (pintype "passive"))
      (node (ref "X3") (pin "8") (pinfunction "KL_8") (pintype "passive"))
    )
    (net (code "55") (name "Net-(X3K-KL)") (class "Default")
      (node (ref "R27") (pin "2") (pinfunction "2_2") (pintype "passive"))
      (node (ref "X3") (pin "9") (pinfunction "KL_9") (pintype "passive"))
    )
    (net (code "56") (name "Net-(X4A-KL)") (class "Default")
      (node (ref "R16") (pin "2") (pinfunction "2_2") (pintype "passive"))
      (node (ref "X4") (pin "1") (pinfunction "KL_1") (pintype "passive"))
    )
    (net (code "57") (name "Net-(X4B-KL)") (class "Default")
      (node (ref "R15") (pin "2") (pinfunction "2_2") (pintype "passive"))
      (node (ref "X4") (pin "2") (pinfunction "KL_2") (pintype "passive"))
    )
    (net (code "58") (name "Net-(X4C-KL)") (class "Default")
      (node (ref "R17") (pin "2") (pinfunction "2_2") (pintype "passive"))
      (node (ref "X4") (pin "3") (pinfunction "KL_3") (pintype "passive"))
    )
    (net (code "59") (name "Net-(X5A-KL)") (class "Default")
      (node (ref "Q5") (pin "1") (pinfunction "S_1") (pintype "passive"))
      (node (ref "Q5") (pin "2") (pinfunction "S_2") (pintype "passive"))
      (node (ref "Q5") (pin "3") (pinfunction "S_3") (pintype "passive"))
      (node (ref "X5") (pin "1") (pinfunction "KL_1") (pintype "passive"))
    )
    (net (code "60") (name "Net-(X5B-KL)") (class "Default")
      (node (ref "Q6") (pin "1") (pinfunction "S_1") (pintype "passive"))
      (node (ref "Q6") (pin "2") (pinfunction "S_2") (pintype "passive"))
      (node (ref "Q6") (pin "3") (pinfunction "S_3") (pintype "passive"))
      (node (ref "X5") (pin "2") (pinfunction "KL_2") (pintype "passive"))
    )
    (net (code "61") (name "Net-(X5C-KL)") (class "Default")
      (node (ref "Q7") (pin "1") (pinfunction "S_1") (pintype "passive"))
      (node (ref "Q7") (pin "2") (pinfunction "S_2") (pintype "passive"))
      (node (ref "Q7") (pin "3") (pinfunction "S_3") (pintype "passive"))
      (node (ref "X5") (pin "3") (pinfunction "KL_3") (pintype "passive"))
    )
    (net (code "62") (name "Net-(X5D-KL)") (class "Default")
      (node (ref "Q8") (pin "1") (pinfunction "S_1") (pintype "passive"))
      (node (ref "Q8") (pin "2") (pinfunction "S_2") (pintype "passive"))
      (node (ref "Q8") (pin "3") (pinfunction "S_3") (pintype "passive"))
      (node (ref "X5") (pin "4") (pinfunction "KL_4") (pintype "passive"))
    )
    (net (code "63") (name "Net-(X5E-KL)") (class "Default")
      (node (ref "Q5") (pin "5") (pinfunction "D_5") (pintype "passive"))
      (node (ref "Q5") (pin "6") (pinfunction "D_6") (pintype "passive"))
      (node (ref "Q5") (pin "7") (pinfunction "D_7") (pintype "passive"))
      (node (ref "Q5") (pin "8") (pinfunction "D_8") (pintype "passive"))
      (node (ref "Q6") (pin "5") (pinfunction "D_5") (pintype "passive"))
      (node (ref "Q6") (pin "6") (pinfunction "D_6") (pintype "passive"))
      (node (ref "Q6") (pin "7") (pinfunction "D_7") (pintype "passive"))
      (node (ref "Q6") (pin "8") (pinfunction "D_8") (pintype "passive"))
      (node (ref "Q7") (pin "5") (pinfunction "D_5") (pintype "passive"))
      (node (ref "Q7") (pin "6") (pinfunction "D_6") (pintype "passive"))
      (node (ref "Q7") (pin "7") (pinfunction "D_7") (pintype "passive"))
      (node (ref "Q7") (pin "8") (pinfunction "D_8") (pintype "passive"))
      (node (ref "Q8") (pin "5") (pinfunction "D_5") (pintype "passive"))
      (node (ref "Q8") (pin "6") (pinfunction "D_6") (pintype "passive"))
      (node (ref "Q8") (pin "7") (pinfunction "D_7") (pintype "passive"))
      (node (ref "Q8") (pin "8") (pinfunction "D_8") (pintype "passive"))
      (node (ref "X5") (pin "5") (pinfunction "KL_5") (pintype "passive"))
    )
    (net (code "64") (name "Net-(X15B-KL)") (class "Default")
      (node (ref "Q2") (pin "1") (pinfunction "S_1") (pintype "passive"))
      (node (ref "Q2") (pin "2") (pinfunction "S_2") (pintype "passive"))
      (node (ref "Q2") (pin "3") (pinfunction "S_3") (pintype "passive"))
      (node (ref "X15") (pin "2") (pinfunction "KL_2") (pintype "passive"))
    )
    (net (code "65") (name "Net-(X15C-KL)") (class "Default")
      (node (ref "Q3") (pin "1") (pinfunction "S_1") (pintype "passive"))
      (node (ref "Q3") (pin "2") (pinfunction "S_2") (pintype "passive"))
      (node (ref "Q3") (pin "3") (pinfunction "S_3") (pintype "passive"))
      (node (ref "X15") (pin "3") (pinfunction "KL_3") (pintype "passive"))
    )
    (net (code "66") (name "Net-(X15D-KL)") (class "Default")
      (node (ref "Q4") (pin "1") (pinfunction "S_1") (pintype "passive"))
      (node (ref "Q4") (pin "2") (pinfunction "S_2") (pintype "passive"))
      (node (ref "Q4") (pin "3") (pinfunction "S_3") (pintype "passive"))
      (node (ref "X15") (pin "4") (pinfunction "KL_4") (pintype "passive"))
    )
    (net (code "67") (name "OIL") (class "Default")
      (node (ref "IC2") (pin "34") (pinfunction "(ADC6)PA6_34") (pintype "bidirectional"))
      (node (ref "Q2") (pin "4") (pinfunction "G_4") (pintype "passive"))
      (node (ref "R42") (pin "2") (pinfunction "2_2") (pintype "passive"))
    )
    (net (code "68") (name "PB0") (class "Default")
      (node (ref "C17") (pin "1") (pinfunction "1_1") (pintype "passive"))
      (node (ref "IC2") (pin "1") (pinfunction "(T0/XCK)PB0_1") (pintype "bidirectional"))
      (node (ref "R32") (pin "1") (pinfunction "1_1") (pintype "passive"))
      (node (ref "T21") (pin "1") (pinfunction "E_1") (pintype "passive"))
    )
    (net (code "69") (name "PB1") (class "Default")
      (node (ref "C15") (pin "1") (pinfunction "1_1") (pintype "passive"))
      (node (ref "IC2") (pin "2") (pinfunction "(T1)PB1_2") (pintype "bidirectional"))
      (node (ref "R40") (pin "1") (pinfunction "1_1") (pintype "passive"))
      (node (ref "T25") (pin "1") (pinfunction "E_1") (pintype "passive"))
    )
    (net (code "70") (name "PB3") (class "Default")
      (node (ref "C13") (pin "1") (pinfunction "1_1") (pintype "passive"))
      (node (ref "IC2") (pin "4") (pinfunction "(AIN1/OC0)PB3_4") (pintype "bidirectional"))
      (node (ref "R38") (pin "1") (pinfunction "1_1") (pintype "passive"))
      (node (ref "T29") (pin "1") (pinfunction "E_1") (pintype "passive"))
    )
    (net (code "71") (name "PB4") (class "Default")
      (node (ref "C12") (pin "1") (pinfunction "1_1") (pintype "passive"))
      (node (ref "IC2") (pin "5") (pinfunction "(SS)PB4_5") (pintype "bidirectional"))
      (node (ref "R37") (pin "1") (pinfunction "1_1") (pintype "passive"))
      (node (ref "T30") (pin "1") (pinfunction "E_1") (pintype "passive"))
    )
    (net (code "72") (name "PB5") (class "Default")
      (node (ref "C9") (pin "1") (pinfunction "1_1") (pintype "passive"))
      (node (ref "IC2") (pin "6") (pinfunction "(MOSI)PB5_6") (pintype "bidirectional"))
      (node (ref "R34") (pin "1") (pinfunction "1_1") (pintype "passive"))
      (node (ref "T23") (pin "1") (pinfunction "E_1") (pintype "passive"))
    )
    (net (code "73") (name "PB6") (class "Default")
      (node (ref "C14") (pin "1") (pinfunction "1_1") (pintype "passive"))
      (node (ref "IC2") (pin "7") (pinfunction "(MISO)PB6_7") (pintype "bidirectional"))
      (node (ref "R39") (pin "1") (pinfunction "1_1") (pintype "passive"))
      (node (ref "T26") (pin "1") (pinfunction "E_1") (pintype "passive"))
    )
    (net (code "74") (name "PB7") (class "Default")
      (node (ref "C11") (pin "1") (pinfunction "1_1") (pintype "passive"))
      (node (ref "IC2") (pin "8") (pinfunction "(SCK)PB7_8") (pintype "bidirectional"))
      (node (ref "R36") (pin "1") (pinfunction "1_1") (pintype "passive"))
      (node (ref "T28") (pin "1") (pinfunction "E_1") (pintype "passive"))
    )
    (net (code "75") (name "PD4") (class "Default")
      (node (ref "C10") (pin "1") (pinfunction "1_1") (pintype "passive"))
      (node (ref "IC2") (pin "18") (pinfunction "(OC1B)PD4_18") (pintype "bidirectional"))
      (node (ref "R35") (pin "1") (pinfunction "1_1") (pintype "passive"))
      (node (ref "T27") (pin "1") (pinfunction "E_1") (pintype "passive"))
    )
    (net (code "76") (name "PD5") (class "Default")
      (node (ref "C8") (pin "1") (pinfunction "1_1") (pintype "passive"))
      (node (ref "IC2") (pin "19") (pinfunction "(OC1A)PD5_19") (pintype "bidirectional"))
      (node (ref "R33") (pin "1") (pinfunction "1_1") (pintype "passive"))
      (node (ref "T22") (pin "1") (pinfunction "E_1") (pintype "passive"))
    )
    (net (code "77") (name "RESET") (class "Default")
      (node (ref "IC2") (pin "9") (pinfunction "RESET_9") (pintype "input"))
      (node (ref "R14") (pin "1") (pinfunction "1_1") (pintype "passive"))
      (node (ref "T24") (pin "1") (pinfunction "E_1") (pintype "passive"))
    )
    (net (code "78") (name "SER") (class "Default")
      (node (ref "IC2") (pin "22") (pinfunction "(SCL)PC0_22") (pintype "bidirectional"))
      (node (ref "IC4") (pin "14") (pinfunction "SER_14") (pintype "input"))
    )
    (net (code "79") (name "VCC") (class "Default")
      (node (ref "C2") (pin "+") (pinfunction "+_+") (pintype "passive"))
      (node (ref "C6") (pin "1") (pinfunction "1_1") (pintype "passive"))
      (node (ref "D1") (pin "A") (pinfunction "A_A") (pintype "passive"))
      (node (ref "IC1") (pin "OUT") (pinfunction "OUT_OUT") (pintype "passive"))
      (node (ref "IC2") (pin "10") (pinfunction "VCC_10") (pintype "power_in"))
      (node (ref "IC2") (pin "30") (pinfunction "AVCC_30") (pintype "power_in"))
      (node (ref "IC3") (pin "OUT") (pinfunction "OUT_OUT") (pintype "passive"))
      (node (ref "IC4") (pin "10") (pinfunction "SCL_10") (pintype "input"))
      (node (ref "Q2") (pin "5") (pinfunction "D_5") (pintype "passive"))
      (node (ref "Q2") (pin "6") (pinfunction "D_6") (pintype "passive"))
      (node (ref "Q2") (pin "7") (pinfunction "D_7") (pintype "passive"))
      (node (ref "Q2") (pin "8") (pinfunction "D_8") (pintype "passive"))
      (node (ref "Q3") (pin "5") (pinfunction "D_5") (pintype "passive"))
      (node (ref "Q3") (pin "6") (pinfunction "D_6") (pintype "passive"))
      (node (ref "Q3") (pin "7") (pinfunction "D_7") (pintype "passive"))
      (node (ref "Q3") (pin "8") (pinfunction "D_8") (pintype "passive"))
      (node (ref "Q4") (pin "5") (pinfunction "D_5") (pintype "passive"))
      (node (ref "Q4") (pin "6") (pinfunction "D_6") (pintype "passive"))
      (node (ref "Q4") (pin "7") (pinfunction "D_7") (pintype "passive"))
      (node (ref "Q4") (pin "8") (pinfunction "D_8") (pintype "passive"))
      (node (ref "R1") (pin "2") (pinfunction "2_2") (pintype "passive"))
      (node (ref "R14") (pin "2") (pinfunction "2_2") (pintype "passive"))
      (node (ref "T21") (pin "3") (pinfunction "C_3") (pintype "passive"))
      (node (ref "T22") (pin "3") (pinfunction "C_3") (pintype "passive"))
      (node (ref "T23") (pin "3") (pinfunction "C_3") (pintype "passive"))
      (node (ref "T25") (pin "3") (pinfunction "C_3") (pintype "passive"))
      (node (ref "T26") (pin "3") (pinfunction "C_3") (pintype "passive"))
      (node (ref "T27") (pin "3") (pinfunction "C_3") (pintype "passive"))
      (node (ref "T28") (pin "3") (pinfunction "C_3") (pintype "passive"))
      (node (ref "T29") (pin "3") (pinfunction "C_3") (pintype "passive"))
      (node (ref "T30") (pin "3") (pinfunction "C_3") (pintype "passive"))
      (node (ref "T5") (pin "3") (pinfunction "C_3") (pintype "passive"))
      (node (ref "T6") (pin "3") (pinfunction "C_3") (pintype "passive"))
      (node (ref "T7") (pin "3") (pinfunction "C_3") (pintype "passive"))
    )
    (net (code "80") (name "WATER") (class "Default")
      (node (ref "IC2") (pin "35") (pinfunction "(ADC5)PA5_35") (pintype "bidirectional"))
      (node (ref "Q3") (pin "4") (pinfunction "G_4") (pintype "passive"))
      (node (ref "R41") (pin "2") (pinfunction "2_2") (pintype "passive"))
    )
    (net (code "81") (name "XTAL1") (class "Default")
      (node (ref "C3") (pin "2") (pinfunction "2_2") (pintype "passive"))
      (node (ref "IC2") (pin "13") (pinfunction "XTAL1_13") (pintype "bidirectional"))
      (node (ref "Q1") (pin "1") (pinfunction "1_1") (pintype "passive"))
    )
    (net (code "82") (name "XTAL2") (class "Default")
      (node (ref "C4") (pin "2") (pinfunction "2_2") (pintype "passive"))
      (node (ref "IC2") (pin "12") (pinfunction "XTAL2_12") (pintype "bidirectional"))
      (node (ref "Q1") (pin "2") (pinfunction "2_2") (pintype "passive"))
    )
    (net (code "83") (name "unconnected-(IC2-(ADC7)PA7-Pad33)") (class "Default")
      (node (ref "IC2") (pin "33") (pinfunction "(ADC7)PA7_33") (pintype "bidirectional"))
    )
    (net (code "84") (name "unconnected-(IC2-(ICP)PD6-Pad20)") (class "Default")
      (node (ref "IC2") (pin "20") (pinfunction "(ICP)PD6_20") (pintype "bidirectional"))
    )
    (net (code "85") (name "unconnected-(IC2-(OC2)PD7-Pad21)") (class "Default")
      (node (ref "IC2") (pin "21") (pinfunction "(OC2)PD7_21") (pintype "bidirectional"))
    )
    (net (code "86") (name "unconnected-(IC2-(RXD)PD0-Pad14)") (class "Default")
      (node (ref "IC2") (pin "14") (pinfunction "(RXD)PD0_14") (pintype "bidirectional"))
    )
    (net (code "87") (name "unconnected-(IC2-(TDI)PC5-Pad27)") (class "Default")
      (node (ref "IC2") (pin "27") (pinfunction "(TDI)PC5_27") (pintype "bidirectional"))
    )
    (net (code "88") (name "unconnected-(IC2-(TDO)PC4-Pad26)") (class "Default")
      (node (ref "IC2") (pin "26") (pinfunction "(TDO)PC4_26") (pintype "bidirectional"))
    )
    (net (code "89") (name "unconnected-(IC2-(TMS)PC3-Pad25)") (class "Default")
      (node (ref "IC2") (pin "25") (pinfunction "(TMS)PC3_25") (pintype "bidirectional"))
    )
    (net (code "90") (name "unconnected-(IC2-(TOSC1)PC6-Pad28)") (class "Default")
      (node (ref "IC2") (pin "28") (pinfunction "(TOSC1)PC6_28") (pintype "bidirectional"))
    )
    (net (code "91") (name "unconnected-(IC2-(TOSC2)PC7-Pad29)") (class "Default")
      (node (ref "IC2") (pin "29") (pinfunction "(TOSC2)PC7_29") (pintype "bidirectional"))
    )
    (net (code "92") (name "unconnected-(IC2-(TXD)PD1-Pad15)") (class "Default")
      (node (ref "IC2") (pin "15") (pinfunction "(TXD)PD1_15") (pintype "bidirectional"))
    )
    (net (code "93") (name "unconnected-(IC4A-QH*-Pad9)") (class "Default")
      (node (ref "IC4") (pin "9") (pinfunction "QH*_9") (pintype "tri_state"))
    )
  )
)
